# ProDoc_P1_2025-09-09.net
KiCad netlist of a schematic drawn in EasyEDA Pro
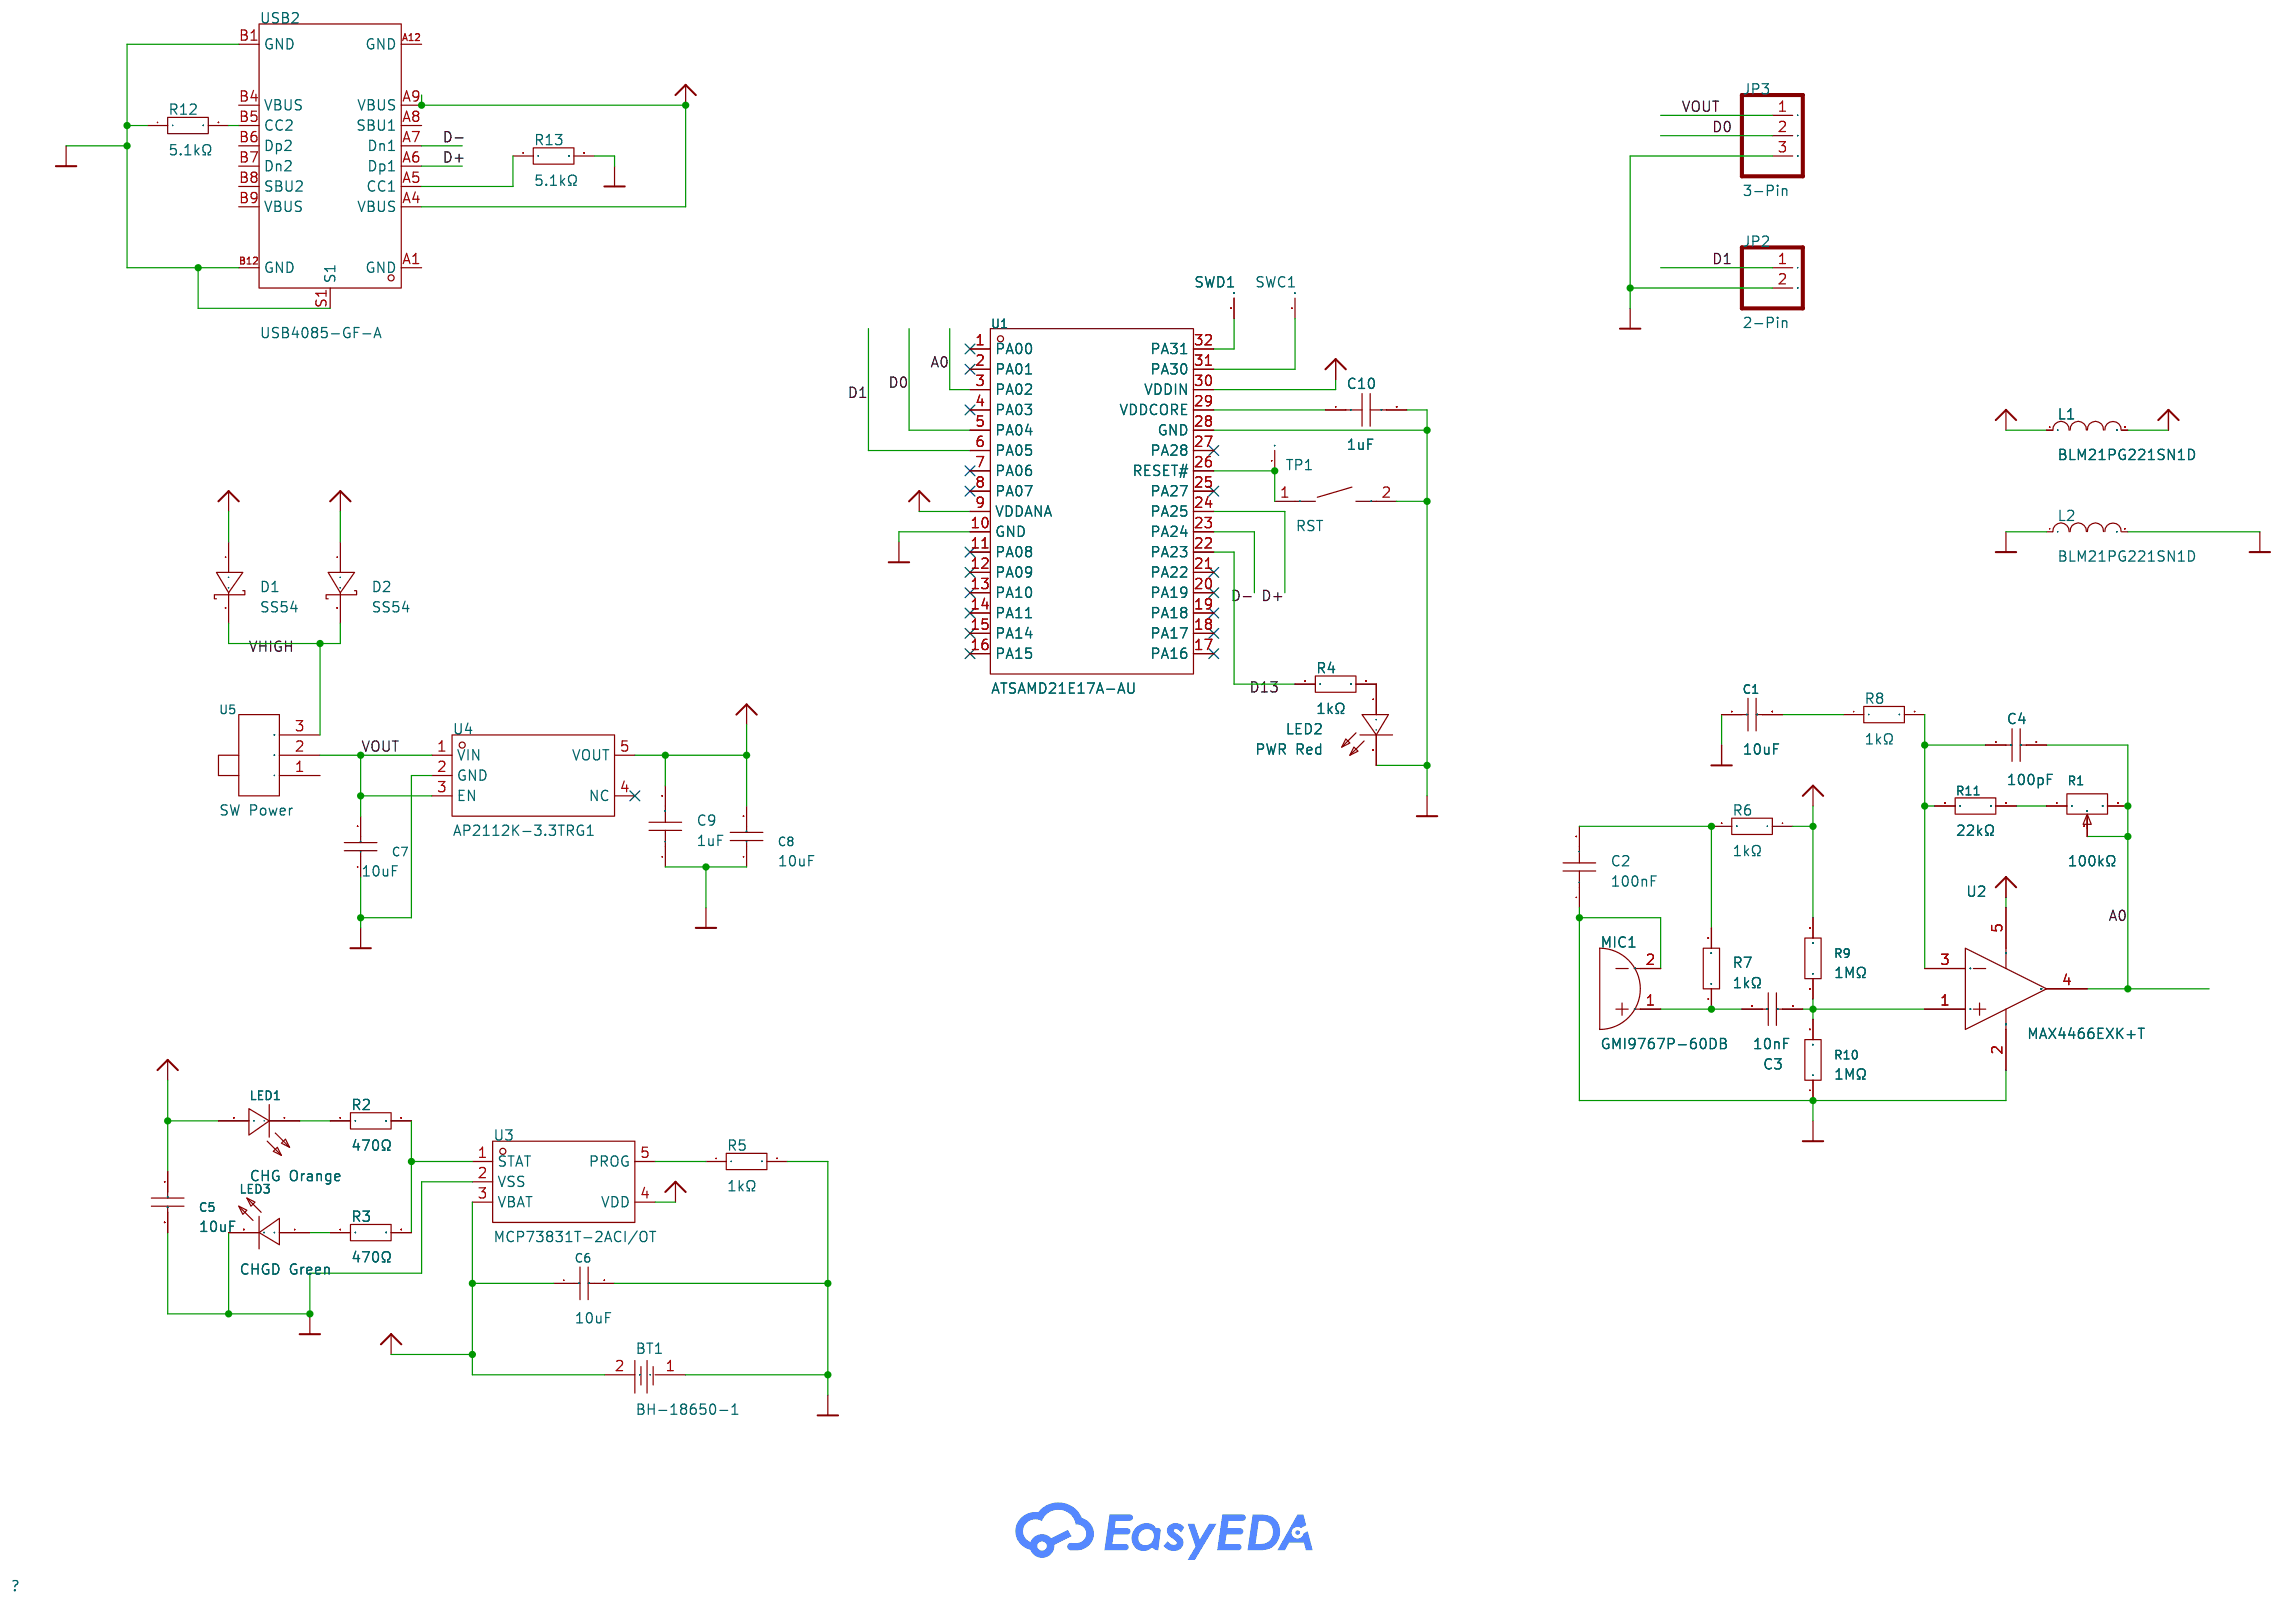
[diagram p0: schematic sheet]

(export (version "E")
  (design (tool "Eeschema 10.0.6"))
  (components
    (comp (ref "B1")
      (value "SWC1")
      (footprint "easyedapro:CON_PAD_ROUND_1.02MM")
      (libsource (lib "easyedapro") (part "PAD_TERMINAL"))
    )
    (comp (ref "B2")
      (value "SWD1")
      (footprint "easyedapro:CON_PAD_ROUND_1.02MM")
      (libsource (lib "easyedapro") (part "PAD_TERMINAL"))
    )
    (comp (ref "B3")
      (value "TP1")
      (footprint "easyedapro:CON_PAD_ROUND_1.02MM")
      (libsource (lib "easyedapro") (part "PAD_TERMINAL"))
    )
    (comp (ref "BT1")
      (value "BH-18650-1")
      (footprint "easyedapro:BAT-TH_BH-18650-A1AJ005")
      (fields (field (name "Manufacturer") "HanElectricity(瀚源)"))
      (libsource (lib "easyedapro") (part "BH-18650-1"))
    )
    (comp (ref "C1")
      (value "10uF")
      (footprint "easyedapro:C0805")
      (description "Capacitance:10uF Tolerance:±10% Tolerance:±10% Voltage Rating:16V Temperature Coefficient:X5R")
      (fields
        (field (name "Manufacturer Part") "CL21A106KOQNNNE")
        (field (name "Manufacturer") "SAMSUNG(三星)")
      )
      (libsource (lib "easyedapro") (part "CL21A106KOQNNNE"))
    )
    (comp (ref "C2")
      (value "100nF")
      (footprint "easyedapro:C0603")
      (description "Capacitance:100nF Tolerance:±10% Tolerance:±10% Voltage Rating:50V Temperature Coefficient:X7R")
      (fields
        (field (name "Manufacturer Part") "CC0603KRX7R9BB104")
        (field (name "Manufacturer") "YAGEO(国巨)")
      )
      (libsource (lib "easyedapro") (part "CC0603KRX7R9BB104"))
    )
    (comp (ref "C3")
      (value "10nF")
      (footprint "easyedapro:C0603")
      (description "Capacitance:10nF Tolerance:±10% Tolerance:±10% Voltage Rating:50V Temperature Coefficient:X7R")
      (fields
        (field (name "Manufacturer Part") "CL10B103KB8NNNC")
        (field (name "Manufacturer") "SAMSUNG(三星)")
      )
      (libsource (lib "easyedapro") (part "CL10B103KB8NNNC"))
    )
    (comp (ref "C4")
      (value "100pF")
      (footprint "easyedapro:C0603")
      (description "Capacitance:100pF Tolerance:±5% Tolerance:±5% Voltage Rating:50V Temperature Coefficient:C0G")
      (fields
        (field (name "Manufacturer Part") "CL10C101JB8NNNC")
        (field (name "Manufacturer") "SAMSUNG(三星)")
      )
      (libsource (lib "easyedapro") (part "CL10C101JB8NNNC"))
    )
    (comp (ref "C5")
      (value "10uF")
      (footprint "easyedapro:C0805")
      (description "Capacitance:10uF Tolerance:±10% Tolerance:±10% Voltage Rating:16V Temperature Coefficient:X5R")
      (fields
        (field (name "Manufacturer Part") "CL21A106KOQNNNE")
        (field (name "Manufacturer") "SAMSUNG(三星)")
      )
      (libsource (lib "easyedapro") (part "CL21A106KOQNNNE"))
    )
    (comp (ref "C6")
      (value "10uF")
      (footprint "easyedapro:C0805")
      (description "Capacitance:10uF Tolerance:±10% Tolerance:±10% Voltage Rating:16V Temperature Coefficient:X5R")
      (fields
        (field (name "Manufacturer Part") "CL21A106KOQNNNE")
        (field (name "Manufacturer") "SAMSUNG(三星)")
      )
      (libsource (lib "easyedapro") (part "CL21A106KOQNNNE"))
    )
    (comp (ref "C7")
      (value "10uF")
      (footprint "easyedapro:C0805")
      (description "Capacitance:10uF Tolerance:±10% Tolerance:±10% Voltage Rating:16V Temperature Coefficient:X5R")
      (fields
        (field (name "Manufacturer Part") "CL21A106KOQNNNE")
        (field (name "Manufacturer") "SAMSUNG(三星)")
      )
      (libsource (lib "easyedapro") (part "CL21A106KOQNNNE"))
    )
    (comp (ref "C8")
      (value "10uF")
      (footprint "easyedapro:C0805")
      (description "Capacitance:10uF Tolerance:±10% Tolerance:±10% Voltage Rating:16V Temperature Coefficient:X5R")
      (fields
        (field (name "Manufacturer Part") "CL21A106KOQNNNE")
        (field (name "Manufacturer") "SAMSUNG(三星)")
      )
      (libsource (lib "easyedapro") (part "CL21A106KOQNNNE"))
    )
    (comp (ref "C9")
      (value "1uF")
      (footprint "easyedapro:C0805")
      (description "Capacitance:1uF Tolerance:±10% Tolerance:±10% Voltage Rating:50V Temperature Coefficient:X7R")
      (fields (field (name "Manufacturer Part") "0805B105K500NT") (field (name "Manufacturer") "FH(风华)"))
      (libsource (lib "easyedapro") (part "0805B105K500NT_C215803"))
    )
    (comp (ref "C10")
      (value "1uF")
      (footprint "easyedapro:C0603")
      (description "Capacitance:1uF Tolerance:±10% Tolerance:±10% Voltage Rating:50V Temperature Coefficient:X5R")
      (fields
        (field (name "Manufacturer Part") "CL10A105KB8NNNC")
        (field (name "Manufacturer") "SAMSUNG(三星)")
      )
      (libsource (lib "easyedapro") (part "CL10A105KB8NNNC"))
    )
    (comp (ref "D1")
      (value "SS54")
      (footprint "easyedapro:SMA_L4.4-W2.8-LS5.4-R-RD")
      (fields (field (name "Manufacturer") "MDD(辰达半导体)"))
      (libsource (lib "easyedapro") (part "SS54_C22452"))
    )
    (comp (ref "D2")
      (value "SS54")
      (footprint "easyedapro:SMA_L4.4-W2.8-LS5.4-R-RD")
      (fields (field (name "Manufacturer") "MDD(辰达半导体)"))
      (libsource (lib "easyedapro") (part "SS54_C22452"))
    )
    (comp (ref "JP2") (value "2-Pin") (libsource (lib "easyedapro") (part "microbuilder_HEADER-1X2_ROUND")))
    (comp (ref "JP3") (value "3-Pin") (libsource (lib "easyedapro") (part "microbuilder_HEADER-1X3_76MIL")))
    (comp (ref "L1")
      (value "BLM21PG221SN1D")
      (footprint "easyedapro:L0805")
      (fields (field (name "Manufacturer") "muRata(村田)"))
      (libsource (lib "easyedapro") (part "BLM21PG221SN1D"))
    )
    (comp (ref "L2")
      (value "BLM21PG221SN1D")
      (footprint "easyedapro:L0805")
      (fields (field (name "Manufacturer") "muRata(村田)"))
      (libsource (lib "easyedapro") (part "BLM21PG221SN1D"))
    )
    (comp (ref "LED1")
      (value "CHG Orange")
      (footprint "easyedapro:LED0805-RD_ORANGE")
      (fields (field (name "Manufacturer Part") "NCD0805O1") (field (name "Manufacturer") "国星光电"))
      (libsource (lib "easyedapro") (part "FC-2012YOXK(5)-600H08"))
    )
    (comp (ref "LED2")
      (value "PWR Red")
      (footprint "easyedapro:LED0805-R-RD")
      (fields (field (name "Manufacturer Part") "NCD0805R1") (field (name "Manufacturer") "国星光电"))
      (libsource (lib "easyedapro") (part "FC-2012HRK-620D"))
    )
    (comp (ref "LED3")
      (value "CHGD Green")
      (footprint "easyedapro:LED0805-R-RD")
      (fields (field (name "Manufacturer Part") "NCD0805G1") (field (name "Manufacturer") "国星光电"))
      (libsource (lib "easyedapro") (part "FC-2012UGK-520D5"))
    )
    (comp (ref "MIC1")
      (value "GMI9767P-60DB")
      (footprint "easyedapro:MIC-TH_BD9.7-P2.54-D0.8-L-FD")
      (fields (field (name "Manufacturer") "INGHAi(赢海)"))
      (libsource (lib "easyedapro") (part "GMI9767P-60DB"))
    )
    (comp (ref "R1")
      (value "100kΩ")
      (footprint "easyedapro:RES-ADJ-SMD_3P-L4.5-W4.5-P2.30-BL-FS")
      (fields (field (name "Manufacturer Part") "3314J-1-104E") (field (name "Manufacturer") "BOURNS"))
      (libsource (lib "easyedapro") (part "3314J-1-104E"))
    )
    (comp (ref "R2")
      (value "470Ω")
      (footprint "easyedapro:R0603")
      (fields
        (field (name "Manufacturer Part") "0603WAF4700T5E")
        (field (name "Manufacturer") "UNI-ROYAL(厚声)")
      )
      (libsource (lib "easyedapro") (part "0603WAF4700T5E"))
    )
    (comp (ref "R3")
      (value "470Ω")
      (footprint "easyedapro:R0603")
      (fields
        (field (name "Manufacturer Part") "0603WAF4700T5E")
        (field (name "Manufacturer") "UNI-ROYAL(厚声)")
      )
      (libsource (lib "easyedapro") (part "0603WAF4700T5E"))
    )
    (comp (ref "R4")
      (value "1kΩ")
      (footprint "easyedapro:R0603")
      (fields
        (field (name "Manufacturer Part") "0603WAF1001T5E")
        (field (name "Manufacturer") "UNI-ROYAL(厚声)")
      )
      (libsource (lib "easyedapro") (part "0603WAF1001T5E"))
    )
    (comp (ref "R5")
      (value "1kΩ")
      (footprint "easyedapro:R0603")
      (fields
        (field (name "Manufacturer Part") "0603WAF1001T5E")
        (field (name "Manufacturer") "UNI-ROYAL(厚声)")
      )
      (libsource (lib "easyedapro") (part "0603WAF1001T5E"))
    )
    (comp (ref "R6")
      (value "1kΩ")
      (footprint "easyedapro:R0603")
      (fields
        (field (name "Manufacturer Part") "0603WAF1001T5E")
        (field (name "Manufacturer") "UNI-ROYAL(厚声)")
      )
      (libsource (lib "easyedapro") (part "0603WAF1001T5E"))
    )
    (comp (ref "R7")
      (value "1kΩ")
      (footprint "easyedapro:R0603")
      (fields
        (field (name "Manufacturer Part") "0603WAF1001T5E")
        (field (name "Manufacturer") "UNI-ROYAL(厚声)")
      )
      (libsource (lib "easyedapro") (part "0603WAF1001T5E"))
    )
    (comp (ref "R8")
      (value "1kΩ")
      (footprint "easyedapro:R0603")
      (fields
        (field (name "Manufacturer Part") "0603WAF1001T5E")
        (field (name "Manufacturer") "UNI-ROYAL(厚声)")
      )
      (libsource (lib "easyedapro") (part "0603WAF1001T5E"))
    )
    (comp (ref "R9")
      (value "1MΩ")
      (footprint "easyedapro:R0402")
      (fields
        (field (name "Manufacturer Part") "0402WGF1004TCE")
        (field (name "Manufacturer") "UNI-ROYAL(厚声)")
      )
      (libsource (lib "easyedapro") (part "0402WGF1004TCE"))
    )
    (comp (ref "R10")
      (value "1MΩ")
      (footprint "easyedapro:R0402")
      (fields
        (field (name "Manufacturer Part") "0402WGF1004TCE")
        (field (name "Manufacturer") "UNI-ROYAL(厚声)")
      )
      (libsource (lib "easyedapro") (part "0402WGF1004TCE"))
    )
    (comp (ref "R11")
      (value "22kΩ")
      (footprint "easyedapro:R0402")
      (fields
        (field (name "Manufacturer Part") "0402WGF2202TCE")
        (field (name "Manufacturer") "UNI-ROYAL(厚声)")
      )
      (libsource (lib "easyedapro") (part "0402WGF2202TCE"))
    )
    (comp (ref "R12")
      (value "5.1kΩ")
      (footprint "easyedapro:R0603")
      (fields
        (field (name "Manufacturer Part") "0603WAF5101T5E")
        (field (name "Manufacturer") "UNI-ROYAL(厚声)")
      )
      (libsource (lib "easyedapro") (part "0603WAF5101T5E"))
    )
    (comp (ref "R13")
      (value "5.1kΩ")
      (footprint "easyedapro:R0603")
      (fields
        (field (name "Manufacturer Part") "0603WAF5101T5E")
        (field (name "Manufacturer") "UNI-ROYAL(厚声)")
      )
      (libsource (lib "easyedapro") (part "0603WAF5101T5E"))
    )
    (comp (ref "SW1")
      (value "RST")
      (footprint "easyedapro:SW-SMD_L3.9-W3.0-P4.45")
      (fields (field (name "Manufacturer Part") "TS-1088-AR02016") (field (name "Manufacturer") "XUNPU(讯普)"))
      (libsource (lib "easyedapro") (part "TS-1088-AR02016"))
    )
    (comp (ref "U1")
      (value "ATSAMD21E17A-AU")
      (footprint "easyedapro:TQFP-32_L7.0-W7.0-P0.80-LS9.0-BL")
      (fields (field (name "Manufacturer") "MICROCHIP(美国微芯)"))
      (libsource (lib "easyedapro") (part "ATSAMD21E17A-AU"))
    )
    (comp (ref "U2")
      (value "MAX4466EXK+T")
      (footprint "easyedapro:SC-70-5_L2.0-W1.3-P0.65-LS2.1-BR")
      (fields (field (name "Manufacturer") "ADI(亚德诺)/MAXIM(美信)"))
      (libsource (lib "easyedapro") (part "MAX4466EXK+T"))
    )
    (comp (ref "U3")
      (value "MCP73831T-2ACI/OT")
      (footprint "easyedapro:SOT-23-5_L3.0-W1.7-P0.95-LS2.8-BL")
      (fields (field (name "Manufacturer") "MICROCHIP(美国微芯)"))
      (libsource (lib "easyedapro") (part "MCP73831T-2ACI/OT"))
    )
    (comp (ref "U4")
      (value "AP2112K-3.3TRG1")
      (footprint "easyedapro:SOT-25-5_L2.9-W1.6-P0.95-LS2.8-BL")
      (fields (field (name "Manufacturer") "DIODES(美台)"))
      (libsource (lib "easyedapro") (part "AP2112K-3.3TRG1"))
    )
    (comp (ref "U5")
      (value "SW Power")
      (footprint "easyedapro:SW-TH_SS-12M12G5")
      (fields
        (field (name "Manufacturer Part") "SS-12M12G5")
        (field (name "Manufacturer") "XKB Connectivity(中国星坤)")
      )
      (libsource (lib "easyedapro") (part "SS-12M12G5"))
    )
    (comp (ref "USB2")
      (value "USB4085-GF-A")
      (footprint "easyedapro:USC-C-SMD_USB4085-GF-A")
      (fields (field (name "Manufacturer") "GCT"))
      (libsource (lib "easyedapro") (part "USB4085-GF-A_C7095263"))
    )
  )
  (nets
    (net (code "1") (name "/A0") (class "Default")
      (node (ref "C4") (pin "2") (pinfunction "2_2") (pintype "input"))
      (node (ref "R1") (pin "2") (pinfunction "2_2") (pintype "input"))
      (node (ref "R1") (pin "3") (pinfunction "3_3") (pintype "input"))
      (node (ref "U1") (pin "3") (pinfunction "PA02_3") (pintype "input"))
      (node (ref "U2") (pin "4") (pinfunction "OUT_4") (pintype "output"))
    )
    (net (code "2") (name "/D+") (class "Default")
      (node (ref "U1") (pin "24") (pinfunction "PA25_24") (pintype "input"))
      (node (ref "USB2") (pin "A6") (pinfunction "Dp1_A6") (pintype "unspecified"))
    )
    (net (code "3") (name "/D-") (class "Default")
      (node (ref "U1") (pin "23") (pinfunction "PA24_23") (pintype "input"))
      (node (ref "USB2") (pin "A7") (pinfunction "Dn1_A7") (pintype "unspecified"))
    )
    (net (code "4") (name "/D0") (class "Default")
      (node (ref "JP3") (pin "2") (pinfunction "2_2") (pintype "unspecified"))
      (node (ref "U1") (pin "5") (pinfunction "PA04_5") (pintype "input"))
    )
    (net (code "5") (name "/D1") (class "Default")
      (node (ref "JP2") (pin "1") (pinfunction "1_1") (pintype "unspecified"))
      (node (ref "U1") (pin "6") (pinfunction "PA05_6") (pintype "input"))
    )
    (net (code "6") (name "/D13") (class "Default")
      (node (ref "R4") (pin "1") (pinfunction "1_1") (pintype "input"))
      (node (ref "U1") (pin "22") (pinfunction "PA23_22") (pintype "input"))
    )
    (net (code "7") (name "/VHIGH") (class "Default")
      (node (ref "D1") (pin "2") (pinfunction "K_2") (pintype "unspecified"))
      (node (ref "D2") (pin "2") (pinfunction "K_2") (pintype "unspecified"))
      (node (ref "U5") (pin "3") (pinfunction "3_3") (pintype "input"))
    )
    (net (code "8") (name "/VOUT") (class "Default")
      (node (ref "C7") (pin "2") (pinfunction "2_2") (pintype "input"))
      (node (ref "JP3") (pin "1") (pinfunction "1_1") (pintype "unspecified"))
      (node (ref "U4") (pin "1") (pinfunction "VIN_1") (pintype "unspecified"))
      (node (ref "U4") (pin "3") (pinfunction "EN_3") (pintype "unspecified"))
      (node (ref "U5") (pin "2") (pinfunction "2_2") (pintype "input"))
    )
    (net (code "9") (name "3.3V") (class "Default")
      (node (ref "C8") (pin "2") (pinfunction "2_2") (pintype "input"))
      (node (ref "C9") (pin "2") (pinfunction "2_2") (pintype "unspecified"))
      (node (ref "L1") (pin "1") (pinfunction "1_1") (pintype "unspecified"))
      (node (ref "U1") (pin "30") (pinfunction "VDDIN_30") (pintype "input"))
      (node (ref "U1") (pin "9") (pinfunction "VDDANA_9") (pintype "input"))
      (node (ref "U4") (pin "5") (pinfunction "VOUT_5") (pintype "unspecified"))
    )
    (net (code "10") (name "AGND") (class "Default")
      (node (ref "C1") (pin "1") (pinfunction "1_1") (pintype "input"))
      (node (ref "C2") (pin "1") (pinfunction "1_1") (pintype "unspecified"))
      (node (ref "L2") (pin "2") (pinfunction "2_2") (pintype "unspecified"))
      (node (ref "MIC1") (pin "2") (pinfunction "2_2") (pintype "unspecified"))
      (node (ref "R10") (pin "1") (pinfunction "1_1") (pintype "input"))
      (node (ref "U2") (pin "2") (pinfunction "GND_2") (pintype "unspecified"))
    )
    (net (code "11") (name "AVCC") (class "Default")
      (node (ref "L1") (pin "2") (pinfunction "2_2") (pintype "unspecified"))
      (node (ref "R6") (pin "1") (pinfunction "1_1") (pintype "input"))
      (node (ref "R9") (pin "2") (pinfunction "2_2") (pintype "input"))
      (node (ref "U2") (pin "5") (pinfunction "VCC_5") (pintype "unspecified"))
    )
    (net (code "12") (name "GND") (class "Default")
      (node (ref "BT1") (pin "1") (pinfunction "1_1") (pintype "input"))
      (node (ref "C10") (pin "2") (pinfunction "2_2") (pintype "unspecified"))
      (node (ref "C5") (pin "2") (pinfunction "2_2") (pintype "input"))
      (node (ref "C6") (pin "2") (pinfunction "2_2") (pintype "input"))
      (node (ref "C7") (pin "1") (pinfunction "1_1") (pintype "input"))
      (node (ref "C8") (pin "1") (pinfunction "1_1") (pintype "input"))
      (node (ref "C9") (pin "1") (pinfunction "1_1") (pintype "unspecified"))
      (node (ref "JP2") (pin "2") (pinfunction "2_2") (pintype "unspecified"))
      (node (ref "JP3") (pin "3") (pinfunction "3_3") (pintype "unspecified"))
      (node (ref "L2") (pin "1") (pinfunction "1_1") (pintype "unspecified"))
      (node (ref "LED2") (pin "2") (pinfunction "-_2") (pintype "unspecified"))
      (node (ref "LED3") (pin "2") (pinfunction "K_2") (pintype "input"))
      (node (ref "R12") (pin "1") (pinfunction "1_1") (pintype "input"))
      (node (ref "R13") (pin "2") (pinfunction "2_2") (pintype "input"))
      (node (ref "R5") (pin "2") (pinfunction "2_2") (pintype "input"))
      (node (ref "SW1") (pin "2") (pinfunction "2_2") (pintype "unspecified"))
      (node (ref "U1") (pin "10") (pinfunction "GND_10") (pintype "input"))
      (node (ref "U1") (pin "28") (pinfunction "GND_28") (pintype "input"))
      (node (ref "U3") (pin "2") (pinfunction "VSS_2") (pintype "unspecified"))
      (node (ref "U4") (pin "2") (pinfunction "GND_2") (pintype "unspecified"))
      (node (ref "USB2") (pin "B1") (pinfunction "GND_B1") (pintype "unspecified"))
      (node (ref "USB2") (pin "B12") (pinfunction "GND_B12") (pintype "unspecified"))
      (node (ref "USB2") (pin "S1") (pinfunction "S1_S1") (pintype "unspecified"))
    )
    (net (code "13") (name "Net-(C1-Pad2)") (class "Default")
      (node (ref "C1") (pin "2") (pinfunction "2_2") (pintype "input"))
      (node (ref "R8") (pin "1") (pinfunction "1_1") (pintype "input"))
    )
    (net (code "14") (name "Net-(C2-Pad2)") (class "Default")
      (node (ref "C2") (pin "2") (pinfunction "2_2") (pintype "unspecified"))
      (node (ref "R6") (pin "2") (pinfunction "2_2") (pintype "input"))
      (node (ref "R7") (pin "2") (pinfunction "2_2") (pintype "input"))
    )
    (net (code "15") (name "Net-(C3-Pad1)") (class "Default")
      (node (ref "C3") (pin "1") (pinfunction "1_1") (pintype "input"))
      (node (ref "MIC1") (pin "1") (pinfunction "1_1") (pintype "unspecified"))
      (node (ref "R7") (pin "1") (pinfunction "1_1") (pintype "input"))
    )
    (net (code "16") (name "Net-(LED1--)") (class "Default")
      (node (ref "LED1") (pin "1") (pinfunction "-_1") (pintype "input"))
      (node (ref "R2") (pin "1") (pinfunction "1_1") (pintype "input"))
    )
    (net (code "17") (name "Net-(LED2-+)") (class "Default")
      (node (ref "LED2") (pin "1") (pinfunction "+_1") (pintype "unspecified"))
      (node (ref "R4") (pin "2") (pinfunction "2_2") (pintype "input"))
    )
    (net (code "18") (name "Net-(LED3-A)") (class "Default")
      (node (ref "LED3") (pin "1") (pinfunction "A_1") (pintype "input"))
      (node (ref "R3") (pin "1") (pinfunction "1_1") (pintype "input"))
    )
    (net (code "19") (name "Net-(R1-Pad1)") (class "Default")
      (node (ref "R1") (pin "1") (pinfunction "1_1") (pintype "input"))
      (node (ref "R11") (pin "2") (pinfunction "2_2") (pintype "input"))
    )
    (net (code "20") (name "Net-(U1-PA30)") (class "Default")
      (node (ref "B1") (pin "P") (pinfunction "P_P") (pintype "input"))
      (node (ref "U1") (pin "31") (pinfunction "PA30_31") (pintype "input"))
    )
    (net (code "21") (name "Net-(U1-PA31)") (class "Default")
      (node (ref "B2") (pin "P") (pinfunction "P_P") (pintype "input"))
      (node (ref "U1") (pin "32") (pinfunction "PA31_32") (pintype "input"))
    )
    (net (code "22") (name "Net-(U1-RESET#)") (class "Default")
      (node (ref "B3") (pin "P") (pinfunction "P_P") (pintype "input"))
      (node (ref "SW1") (pin "1") (pinfunction "1_1") (pintype "unspecified"))
      (node (ref "U1") (pin "26") (pinfunction "RESET#_26") (pintype "input"))
    )
    (net (code "23") (name "Net-(U1-VDDCORE)") (class "Default")
      (node (ref "C10") (pin "1") (pinfunction "1_1") (pintype "unspecified"))
      (node (ref "U1") (pin "29") (pinfunction "VDDCORE_29") (pintype "input"))
    )
    (net (code "24") (name "Net-(U2-IN+)") (class "Default")
      (node (ref "C3") (pin "2") (pinfunction "2_2") (pintype "input"))
      (node (ref "R10") (pin "2") (pinfunction "2_2") (pintype "input"))
      (node (ref "R9") (pin "1") (pinfunction "1_1") (pintype "input"))
      (node (ref "U2") (pin "1") (pinfunction "IN+_1") (pintype "unspecified"))
    )
    (net (code "25") (name "Net-(U2-IN-)") (class "Default")
      (node (ref "C4") (pin "1") (pinfunction "1_1") (pintype "input"))
      (node (ref "R11") (pin "1") (pinfunction "1_1") (pintype "input"))
      (node (ref "R8") (pin "2") (pinfunction "2_2") (pintype "input"))
      (node (ref "U2") (pin "3") (pinfunction "IN-_3") (pintype "unspecified"))
    )
    (net (code "26") (name "Net-(U3-PROG)") (class "Default")
      (node (ref "R5") (pin "1") (pinfunction "1_1") (pintype "input"))
      (node (ref "U3") (pin "5") (pinfunction "PROG_5") (pintype "unspecified"))
    )
    (net (code "27") (name "Net-(U3-STAT)") (class "Default")
      (node (ref "R2") (pin "2") (pinfunction "2_2") (pintype "input"))
      (node (ref "R3") (pin "2") (pinfunction "2_2") (pintype "input"))
      (node (ref "U3") (pin "1") (pinfunction "STAT_1") (pintype "unspecified"))
    )
    (net (code "28") (name "Net-(USB2-CC1)") (class "Default")
      (node (ref "R13") (pin "1") (pinfunction "1_1") (pintype "input"))
      (node (ref "USB2") (pin "A5") (pinfunction "CC1_A5") (pintype "unspecified"))
    )
    (net (code "29") (name "Net-(USB2-CC2)") (class "Default")
      (node (ref "R12") (pin "2") (pinfunction "2_2") (pintype "input"))
      (node (ref "USB2") (pin "B5") (pinfunction "CC2_B5") (pintype "unspecified"))
    )
    (net (code "30") (name "VBAT") (class "Default")
      (node (ref "BT1") (pin "2") (pinfunction "2_2") (pintype "input"))
      (node (ref "C6") (pin "1") (pinfunction "1_1") (pintype "input"))
      (node (ref "D1") (pin "1") (pinfunction "A_1") (pintype "unspecified"))
      (node (ref "U3") (pin "3") (pinfunction "VBAT_3") (pintype "unspecified"))
    )
    (net (code "31") (name "VBUS") (class "Default")
      (node (ref "C5") (pin "1") (pinfunction "1_1") (pintype "input"))
      (node (ref "D2") (pin "1") (pinfunction "A_1") (pintype "unspecified"))
      (node (ref "LED1") (pin "2") (pinfunction "+_2") (pintype "input"))
      (node (ref "U3") (pin "4") (pinfunction "VDD_4") (pintype "unspecified"))
      (node (ref "USB2") (pin "A4") (pinfunction "VBUS_A4") (pintype "unspecified"))
      (node (ref "USB2") (pin "A9") (pinfunction "VBUS_A9") (pintype "unspecified"))
    )
    (net (code "32") (name "unconnected-(U1-PA00-Pad1)") (class "Default")
      (node (ref "U1") (pin "1") (pinfunction "PA00_1") (pintype "input+no_connect"))
    )
    (net (code "33") (name "unconnected-(U1-PA01-Pad2)") (class "Default")
      (node (ref "U1") (pin "2") (pinfunction "PA01_2") (pintype "input+no_connect"))
    )
    (net (code "34") (name "unconnected-(U1-PA03-Pad4)") (class "Default")
      (node (ref "U1") (pin "4") (pinfunction "PA03_4") (pintype "input+no_connect"))
    )
    (net (code "35") (name "unconnected-(U1-PA06-Pad7)") (class "Default")
      (node (ref "U1") (pin "7") (pinfunction "PA06_7") (pintype "input+no_connect"))
    )
    (net (code "36") (name "unconnected-(U1-PA07-Pad8)") (class "Default")
      (node (ref "U1") (pin "8") (pinfunction "PA07_8") (pintype "input+no_connect"))
    )
    (net (code "37") (name "unconnected-(U1-PA08-Pad11)") (class "Default")
      (node (ref "U1") (pin "11") (pinfunction "PA08_11") (pintype "input+no_connect"))
    )
    (net (code "38") (name "unconnected-(U1-PA09-Pad12)") (class "Default")
      (node (ref "U1") (pin "12") (pinfunction "PA09_12") (pintype "input+no_connect"))
    )
    (net (code "39") (name "unconnected-(U1-PA10-Pad13)") (class "Default")
      (node (ref "U1") (pin "13") (pinfunction "PA10_13") (pintype "input+no_connect"))
    )
    (net (code "40") (name "unconnected-(U1-PA11-Pad14)") (class "Default")
      (node (ref "U1") (pin "14") (pinfunction "PA11_14") (pintype "input+no_connect"))
    )
    (net (code "41") (name "unconnected-(U1-PA14-Pad15)") (class "Default")
      (node (ref "U1") (pin "15") (pinfunction "PA14_15") (pintype "input+no_connect"))
    )
    (net (code "42") (name "unconnected-(U1-PA15-Pad16)") (class "Default")
      (node (ref "U1") (pin "16") (pinfunction "PA15_16") (pintype "input+no_connect"))
    )
    (net (code "43") (name "unconnected-(U1-PA16-Pad17)") (class "Default")
      (node (ref "U1") (pin "17") (pinfunction "PA16_17") (pintype "input+no_connect"))
    )
    (net (code "44") (name "unconnected-(U1-PA17-Pad18)") (class "Default")
      (node (ref "U1") (pin "18") (pinfunction "PA17_18") (pintype "input+no_connect"))
    )
    (net (code "45") (name "unconnected-(U1-PA18-Pad19)") (class "Default")
      (node (ref "U1") (pin "19") (pinfunction "PA18_19") (pintype "input+no_connect"))
    )
    (net (code "46") (name "unconnected-(U1-PA19-Pad20)") (class "Default")
      (node (ref "U1") (pin "20") (pinfunction "PA19_20") (pintype "input+no_connect"))
    )
    (net (code "47") (name "unconnected-(U1-PA22-Pad21)") (class "Default")
      (node (ref "U1") (pin "21") (pinfunction "PA22_21") (pintype "input+no_connect"))
    )
    (net (code "48") (name "unconnected-(U1-PA27-Pad25)") (class "Default")
      (node (ref "U1") (pin "25") (pinfunction "PA27_25") (pintype "input+no_connect"))
    )
    (net (code "49") (name "unconnected-(U1-PA28-Pad27)") (class "Default")
      (node (ref "U1") (pin "27") (pinfunction "PA28_27") (pintype "input+no_connect"))
    )
    (net (code "50") (name "unconnected-(U4-NC-Pad4)") (class "Default")
      (node (ref "U4") (pin "4") (pinfunction "NC_4") (pintype "unspecified+no_connect"))
    )
    (net (code "51") (name "unconnected-(U5-Pad1)") (class "Default")
      (node (ref "U5") (pin "1") (pinfunction "1_1") (pintype "input"))
    )
    (net (code "52") (name "unconnected-(USB2-Dn2-PadB7)") (class "Default")
      (node (ref "USB2") (pin "B7") (pinfunction "Dn2_B7") (pintype "unspecified"))
    )
    (net (code "53") (name "unconnected-(USB2-Dp2-PadB6)") (class "Default")
      (node (ref "USB2") (pin "B6") (pinfunction "Dp2_B6") (pintype "unspecified"))
    )
    (net (code "54") (name "unconnected-(USB2-GND-PadA1)") (class "Default")
      (node (ref "USB2") (pin "A1") (pinfunction "GND_A1") (pintype "unspecified"))
    )
    (net (code "55") (name "unconnected-(USB2-GND-PadA12)") (class "Default")
      (node (ref "USB2") (pin "A12") (pinfunction "GND_A12") (pintype "unspecified"))
    )
    (net (code "56") (name "unconnected-(USB2-SBU1-PadA8)") (class "Default")
      (node (ref "USB2") (pin "A8") (pinfunction "SBU1_A8") (pintype "unspecified"))
    )
    (net (code "57") (name "unconnected-(USB2-SBU2-PadB8)") (class "Default")
      (node (ref "USB2") (pin "B8") (pinfunction "SBU2_B8") (pintype "unspecified"))
    )
    (net (code "58") (name "unconnected-(USB2-VBUS-PadB4)") (class "Default")
      (node (ref "USB2") (pin "B4") (pinfunction "VBUS_B4") (pintype "unspecified"))
    )
    (net (code "59") (name "unconnected-(USB2-VBUS-PadB9)") (class "Default")
      (node (ref "USB2") (pin "B9") (pinfunction "VBUS_B9") (pintype "unspecified"))
    )
  )
)
